# main.net
KiCad netlist of a schematic drawn in EAGLE
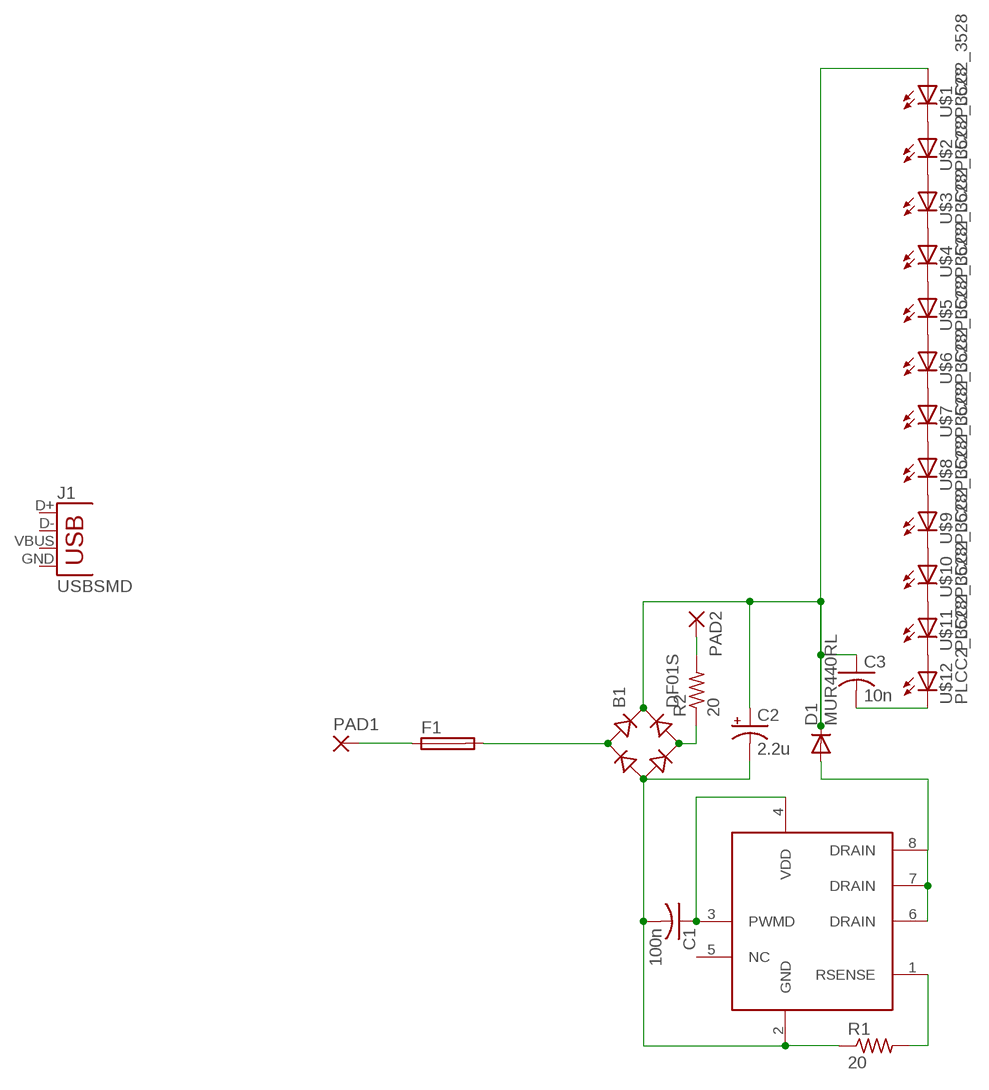
[diagram p0: schematic, sheet 1]

(export (version "E")
  (design (tool "Eeschema 10.0.6"))
  (components
    (comp (ref "B1")
      (value "DF01S")
      (footprint "eagle-import:DFS")
      (libsource (lib "eagle-import") (part "DFS01"))
    )
    (comp (ref "C1")
      (value "100n")
      (footprint "eagle-import:C0603")
      (libsource (lib "eagle-import") (part "C-USC0603"))
    )
    (comp (ref "C2")
      (value "2.2u")
      (footprint "eagle-import:E3,5-8")
      (libsource (lib "eagle-import") (part "CPOL-USE3.5-8"))
    )
    (comp (ref "C3")
      (value "10n")
      (footprint "eagle-import:C025-025X050")
      (libsource (lib "eagle-import") (part "C-US025-025X050"))
    )
    (comp (ref "D1")
      (value "MUR440RL")
      (footprint "eagle-import:C2673")
      (libsource (lib "eagle-import") (part "MUR440RL"))
    )
    (comp (ref "F1")
      (value "TE5")
      (footprint "eagle-import:TE5")
      (libsource (lib "eagle-import") (part "TE5"))
    )
    (comp (ref "J1")
      (value "USBSMD")
      (footprint "eagle-import:USB-MINIB")
      (libsource (lib "eagle-import") (part "USBSMD"))
    )
    (comp (ref "PAD1")
      (value "2,54/1,0")
      (footprint "eagle-import:2,54_1,0")
      (libsource (lib "eagle-import") (part "2,54/1,0"))
    )
    (comp (ref "PAD2")
      (value "2,54/1,0")
      (footprint "eagle-import:2,54_1,0")
      (libsource (lib "eagle-import") (part "2,54/1,0"))
    )
    (comp (ref "R1")
      (value "20")
      (footprint "eagle-import:R0805")
      (libsource (lib "eagle-import") (part "R-US_R0805"))
    )
    (comp (ref "R2")
      (value "20")
      (footprint "eagle-import:R0805")
      (libsource (lib "eagle-import") (part "R-US_R0805"))
    )
    (comp (ref "U$1")
      (value "PLCC2_3528")
      (footprint "eagle-import:PLCC2_3528")
      (libsource (lib "eagle-import") (part "PLCC2_3528"))
    )
    (comp (ref "U$2")
      (value "PLCC2_3528")
      (footprint "eagle-import:PLCC2_3528")
      (libsource (lib "eagle-import") (part "PLCC2_3528"))
    )
    (comp (ref "U$3")
      (value "PLCC2_3528")
      (footprint "eagle-import:PLCC2_3528")
      (libsource (lib "eagle-import") (part "PLCC2_3528"))
    )
    (comp (ref "U$4")
      (value "PLCC2_3528")
      (footprint "eagle-import:PLCC2_3528")
      (libsource (lib "eagle-import") (part "PLCC2_3528"))
    )
    (comp (ref "U$5")
      (value "PLCC2_3528")
      (footprint "eagle-import:PLCC2_3528")
      (libsource (lib "eagle-import") (part "PLCC2_3528"))
    )
    (comp (ref "U$6")
      (value "PLCC2_3528")
      (footprint "eagle-import:PLCC2_3528")
      (libsource (lib "eagle-import") (part "PLCC2_3528"))
    )
    (comp (ref "U$7")
      (value "PLCC2_3528")
      (footprint "eagle-import:PLCC2_3528")
      (libsource (lib "eagle-import") (part "PLCC2_3528"))
    )
    (comp (ref "U$8")
      (value "PLCC2_3528")
      (footprint "eagle-import:PLCC2_3528")
      (libsource (lib "eagle-import") (part "PLCC2_3528"))
    )
    (comp (ref "U$9")
      (value "PLCC2_3528")
      (footprint "eagle-import:PLCC2_3528")
      (libsource (lib "eagle-import") (part "PLCC2_3528"))
    )
    (comp (ref "U$10")
      (value "PLCC2_3528")
      (footprint "eagle-import:PLCC2_3528")
      (libsource (lib "eagle-import") (part "PLCC2_3528"))
    )
    (comp (ref "U$11")
      (value "PLCC2_3528")
      (footprint "eagle-import:PLCC2_3528")
      (libsource (lib "eagle-import") (part "PLCC2_3528"))
    )
    (comp (ref "U$12")
      (value "PLCC2_3528")
      (footprint "eagle-import:PLCC2_3528")
      (libsource (lib "eagle-import") (part "PLCC2_3528"))
    )
    (comp (ref "U$13")
      (value "HV9925")
      (footprint "eagle-import:SOIC-8")
      (libsource (lib "eagle-import") (part "HV9925"))
    )
  )
  (nets
    (net (code "1") (name "Net-(B1-PadAC1)") (class "Default")
      (node (ref "B1") (pin "AC1") (pinfunction "AC1_AC1") (pintype "passive"))
      (node (ref "F1") (pin "2") (pinfunction "2_2") (pintype "passive"))
    )
    (net (code "2") (name "Net-(B1-PadAC2)") (class "Default")
      (node (ref "B1") (pin "AC2") (pinfunction "AC2_AC2") (pintype "passive"))
      (node (ref "R2") (pin "1") (pinfunction "1_1") (pintype "passive"))
    )
    (net (code "3") (name "Net-(D1-PadA)") (class "Default")
      (node (ref "D1") (pin "A") (pinfunction "A_A") (pintype "passive"))
      (node (ref "U$13") (pin "6") (pinfunction "DRAIN_6") (pintype "bidirectional"))
      (node (ref "U$13") (pin "7") (pinfunction "DRAIN_7") (pintype "bidirectional"))
      (node (ref "U$13") (pin "8") (pinfunction "DRAIN_8") (pintype "bidirectional"))
    )
    (net (code "4") (name "Net-(PAD1-P)") (class "Default")
      (node (ref "F1") (pin "1") (pinfunction "1_1") (pintype "passive"))
      (node (ref "PAD1") (pin "1") (pinfunction "P_1") (pintype "passive"))
    )
    (net (code "5") (name "Net-(PAD2-P)") (class "Default")
      (node (ref "PAD2") (pin "1") (pinfunction "P_1") (pintype "passive"))
      (node (ref "R2") (pin "2") (pinfunction "2_2") (pintype "passive"))
    )
    (net (code "6") (name "Net-(U$1-A)") (class "Default")
      (node (ref "B1") (pin "+") (pinfunction "+_+") (pintype "passive"))
      (node (ref "C2") (pin "+") (pinfunction "+_+") (pintype "passive"))
      (node (ref "C3") (pin "1") (pinfunction "1_1") (pintype "passive"))
      (node (ref "D1") (pin "C") (pinfunction "C_C") (pintype "passive"))
      (node (ref "U$1") (pin "P$1") (pinfunction "A_P$1") (pintype "passive"))
    )
    (net (code "7") (name "Net-(U$1-C)") (class "Default")
      (node (ref "U$1") (pin "P$2") (pinfunction "C_P$2") (pintype "passive"))
      (node (ref "U$2") (pin "P$1") (pinfunction "A_P$1") (pintype "passive"))
    )
    (net (code "8") (name "Net-(U$2-C)") (class "Default")
      (node (ref "U$2") (pin "P$2") (pinfunction "C_P$2") (pintype "passive"))
      (node (ref "U$3") (pin "P$1") (pinfunction "A_P$1") (pintype "passive"))
    )
    (net (code "9") (name "Net-(U$3-C)") (class "Default")
      (node (ref "U$3") (pin "P$2") (pinfunction "C_P$2") (pintype "passive"))
      (node (ref "U$4") (pin "P$1") (pinfunction "A_P$1") (pintype "passive"))
    )
    (net (code "10") (name "Net-(U$4-C)") (class "Default")
      (node (ref "U$4") (pin "P$2") (pinfunction "C_P$2") (pintype "passive"))
      (node (ref "U$5") (pin "P$1") (pinfunction "A_P$1") (pintype "passive"))
    )
    (net (code "11") (name "Net-(U$5-C)") (class "Default")
      (node (ref "U$5") (pin "P$2") (pinfunction "C_P$2") (pintype "passive"))
      (node (ref "U$6") (pin "P$1") (pinfunction "A_P$1") (pintype "passive"))
    )
    (net (code "12") (name "Net-(U$6-C)") (class "Default")
      (node (ref "U$6") (pin "P$2") (pinfunction "C_P$2") (pintype "passive"))
      (node (ref "U$7") (pin "P$1") (pinfunction "A_P$1") (pintype "passive"))
    )
    (net (code "13") (name "Net-(U$7-C)") (class "Default")
      (node (ref "U$7") (pin "P$2") (pinfunction "C_P$2") (pintype "passive"))
      (node (ref "U$8") (pin "P$1") (pinfunction "A_P$1") (pintype "passive"))
    )
    (net (code "14") (name "Net-(U$8-C)") (class "Default")
      (node (ref "U$8") (pin "P$2") (pinfunction "C_P$2") (pintype "passive"))
      (node (ref "U$9") (pin "P$1") (pinfunction "A_P$1") (pintype "passive"))
    )
    (net (code "15") (name "Net-(U$10-A)") (class "Default")
      (node (ref "U$10") (pin "P$1") (pinfunction "A_P$1") (pintype "passive"))
      (node (ref "U$9") (pin "P$2") (pinfunction "C_P$2") (pintype "passive"))
    )
    (net (code "16") (name "Net-(U$10-C)") (class "Default")
      (node (ref "U$10") (pin "P$2") (pinfunction "C_P$2") (pintype "passive"))
      (node (ref "U$11") (pin "P$1") (pinfunction "A_P$1") (pintype "passive"))
    )
    (net (code "17") (name "Net-(U$11-C)") (class "Default")
      (node (ref "U$11") (pin "P$2") (pinfunction "C_P$2") (pintype "passive"))
      (node (ref "U$12") (pin "P$1") (pinfunction "A_P$1") (pintype "passive"))
    )
    (net (code "18") (name "Net-(U$12-C)") (class "Default")
      (node (ref "C3") (pin "2") (pinfunction "2_2") (pintype "passive"))
      (node (ref "U$12") (pin "P$2") (pinfunction "C_P$2") (pintype "passive"))
    )
    (net (code "19") (name "Net-(U$13-GND)") (class "Default")
      (node (ref "B1") (pin "-") (pinfunction "-_-") (pintype "passive"))
      (node (ref "C1") (pin "2") (pinfunction "2_2") (pintype "passive"))
      (node (ref "C2") (pin "-") (pinfunction "-_-") (pintype "passive"))
      (node (ref "R1") (pin "1") (pinfunction "1_1") (pintype "passive"))
      (node (ref "U$13") (pin "2") (pinfunction "GND_2") (pintype "bidirectional"))
    )
    (net (code "20") (name "Net-(U$13-PWMD)") (class "Default")
      (node (ref "C1") (pin "1") (pinfunction "1_1") (pintype "passive"))
      (node (ref "U$13") (pin "3") (pinfunction "PWMD_3") (pintype "bidirectional"))
      (node (ref "U$13") (pin "4") (pinfunction "VDD_4") (pintype "bidirectional"))
    )
    (net (code "21") (name "Net-(U$13-RSENSE)") (class "Default")
      (node (ref "R1") (pin "2") (pinfunction "2_2") (pintype "passive"))
      (node (ref "U$13") (pin "1") (pinfunction "RSENSE_1") (pintype "bidirectional"))
    )
    (net (code "22") (name "unconnected-(J1-PadD+)") (class "Default")
      (node (ref "J1") (pin "D+") (pinfunction "D+_D+") (pintype "bidirectional"))
    )
    (net (code "23") (name "unconnected-(J1-PadD-)") (class "Default")
      (node (ref "J1") (pin "D-") (pinfunction "D-_D-") (pintype "bidirectional"))
    )
    (net (code "24") (name "unconnected-(J1-PadGND)") (class "Default")
      (node (ref "J1") (pin "GND") (pinfunction "GND_GND") (pintype "bidirectional"))
    )
    (net (code "25") (name "unconnected-(J1-PadVBUS)") (class "Default")
      (node (ref "J1") (pin "VBUS") (pinfunction "VBUS_VBUS") (pintype "bidirectional"))
    )
    (net (code "26") (name "unconnected-(U$13-NC-Pad5)") (class "Default")
      (node (ref "U$13") (pin "5") (pinfunction "NC_5") (pintype "bidirectional"))
    )
  )
)
